# schematic.net
KiCad netlist of a schematic drawn in EAGLE
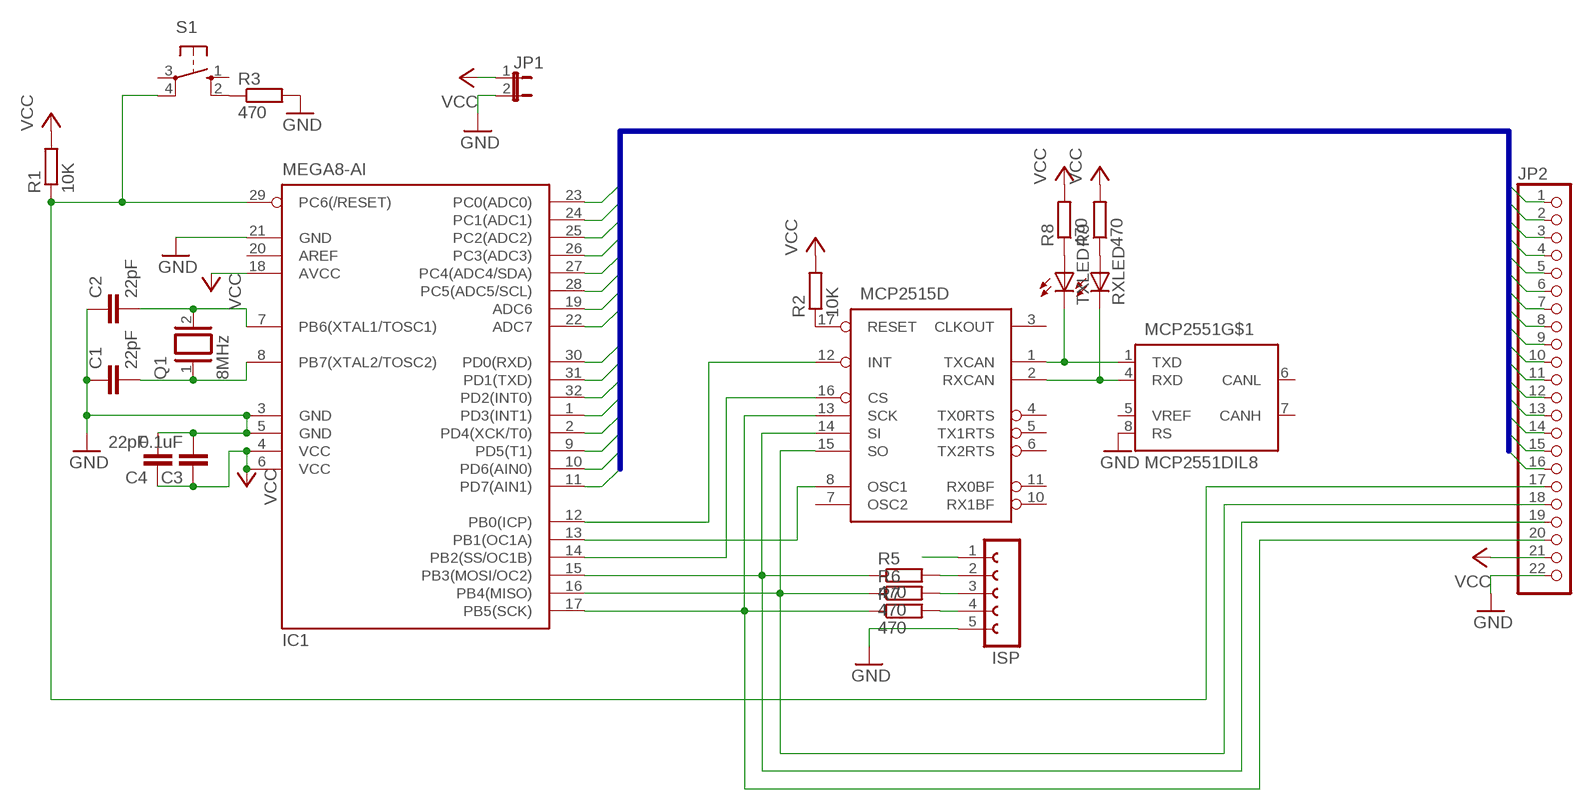
[diagram p0: schematic, sheet 1]

(export (version "E")
  (design (tool "Eeschema 10.0.6"))
  (components
    (comp (ref "C1")
      (value "22pF")
      (footprint "eagle-import:C0603")
      (libsource (lib "eagle-import") (part "C-EUC0603"))
    )
    (comp (ref "C2")
      (value "22pF")
      (footprint "eagle-import:C0603")
      (libsource (lib "eagle-import") (part "C-EUC0603"))
    )
    (comp (ref "C3")
      (value "0.1uF")
      (footprint "eagle-import:C0603")
      (libsource (lib "eagle-import") (part "C-EUC0603"))
    )
    (comp (ref "C4")
      (value "22pF")
      (footprint "eagle-import:C0603")
      (libsource (lib "eagle-import") (part "C-EUC0603"))
    )
    (comp (ref "IC1")
      (value "MEGA8-AI")
      (footprint "eagle-import:TQFP32-08")
      (fields (field (name "MPN") "ATMEGA8-16AU") (field (name "OC_NEWARK") "unknown"))
      (libsource (lib "eagle-import") (part "MEGA8-AI"))
    )
    (comp (ref "ISP")
      (value "FE05-1")
      (footprint "eagle-import:FE05-1")
      (libsource (lib "eagle-import") (part "FE05-1"))
    )
    (comp (ref "JP1")
      (value "JUMPER-2PTH")
      (footprint "eagle-import:1X02")
      (libsource (lib "eagle-import") (part "JUMPER-2PTH"))
    )
    (comp (ref "JP2")
      (value "PINHD-1X22/90")
      (footprint "eagle-import:1X22_90")
      (libsource (lib "eagle-import") (part "PINHD-1X22/90"))
    )
    (comp (ref "MCP2515")
      (value "MCP2515P")
      (footprint "eagle-import:DIL18")
      (libsource (lib "eagle-import") (part "MCP2515P"))
    )
    (comp (ref "MCP2551")
      (value "MCP2551DIL8")
      (footprint "eagle-import:DIL08")
      (libsource (lib "eagle-import") (part "MCP2551DIL8"))
    )
    (comp (ref "Q1")
      (value "8MHz")
      (footprint "eagle-import:QS")
      (libsource (lib "eagle-import") (part "XTAL/S"))
    )
    (comp (ref "R1")
      (value "10K")
      (footprint "eagle-import:R0603")
      (libsource (lib "eagle-import") (part "R-EU_R0603"))
    )
    (comp (ref "R2")
      (value "10K")
      (footprint "eagle-import:R0603")
      (libsource (lib "eagle-import") (part "R-EU_R0603"))
    )
    (comp (ref "R3")
      (value "470")
      (footprint "eagle-import:R0603")
      (libsource (lib "eagle-import") (part "R-EU_R0603"))
    )
    (comp (ref "R5")
      (value "470")
      (footprint "eagle-import:R0603")
      (libsource (lib "eagle-import") (part "R-EU_R0603"))
    )
    (comp (ref "R6")
      (value "470")
      (footprint "eagle-import:R0603")
      (libsource (lib "eagle-import") (part "R-EU_R0603"))
    )
    (comp (ref "R7")
      (value "470")
      (footprint "eagle-import:R0603")
      (libsource (lib "eagle-import") (part "R-EU_R0603"))
    )
    (comp (ref "R8")
      (value "470")
      (footprint "eagle-import:R0603")
      (libsource (lib "eagle-import") (part "R-EU_R0603"))
    )
    (comp (ref "R9")
      (value "470")
      (footprint "eagle-import:R0603")
      (libsource (lib "eagle-import") (part "R-EU_R0603"))
    )
    (comp (ref "RXLED")
      (value "LED")
      (footprint "eagle-import:SMARTLED-TTW")
      (libsource (lib "eagle-import") (part "LED"))
    )
    (comp (ref "S1")
      (value "10-XX")
      (footprint "eagle-import:B3F-10XX")
      (fields (field (name "MPN") "B3F-1000"))
      (libsource (lib "eagle-import") (part "10-XX"))
    )
    (comp (ref "TXLED")
      (value "LED")
      (footprint "eagle-import:SMARTLED-TTW")
      (libsource (lib "eagle-import") (part "LED"))
    )
  )
  (nets
    (net (code "1") (name "/PC0") (class "Default")
      (node (ref "IC1") (pin "23") (pinfunction "PC0(ADC0)_23") (pintype "bidirectional"))
      (node (ref "JP2") (pin "1") (pinfunction "1_1") (pintype "passive"))
    )
    (net (code "2") (name "/PC1") (class "Default")
      (node (ref "IC1") (pin "24") (pinfunction "PC1(ADC1)_24") (pintype "bidirectional"))
      (node (ref "JP2") (pin "2") (pinfunction "2_2") (pintype "passive"))
    )
    (net (code "3") (name "/PC2") (class "Default")
      (node (ref "IC1") (pin "25") (pinfunction "PC2(ADC2)_25") (pintype "bidirectional"))
      (node (ref "JP2") (pin "3") (pinfunction "3_3") (pintype "passive"))
    )
    (net (code "4") (name "/PC3") (class "Default")
      (node (ref "IC1") (pin "26") (pinfunction "PC3(ADC3)_26") (pintype "bidirectional"))
      (node (ref "JP2") (pin "4") (pinfunction "4_4") (pintype "passive"))
    )
    (net (code "5") (name "/PC4") (class "Default")
      (node (ref "IC1") (pin "27") (pinfunction "PC4(ADC4/SDA)_27") (pintype "bidirectional"))
      (node (ref "JP2") (pin "5") (pinfunction "5_5") (pintype "passive"))
    )
    (net (code "6") (name "/PC5") (class "Default")
      (node (ref "IC1") (pin "28") (pinfunction "PC5(ADC5/SCL)_28") (pintype "bidirectional"))
      (node (ref "JP2") (pin "6") (pinfunction "6_6") (pintype "passive"))
    )
    (net (code "7") (name "/PC6") (class "Default")
      (node (ref "IC1") (pin "19") (pinfunction "ADC6_19") (pintype "bidirectional"))
      (node (ref "JP2") (pin "7") (pinfunction "7_7") (pintype "passive"))
    )
    (net (code "8") (name "/PC7") (class "Default")
      (node (ref "IC1") (pin "22") (pinfunction "ADC7_22") (pintype "bidirectional"))
      (node (ref "JP2") (pin "8") (pinfunction "8_8") (pintype "passive"))
    )
    (net (code "9") (name "/PD0") (class "Default")
      (node (ref "IC1") (pin "30") (pinfunction "PD0(RXD)_30") (pintype "bidirectional"))
      (node (ref "JP2") (pin "9") (pinfunction "9_9") (pintype "passive"))
    )
    (net (code "10") (name "/PD1") (class "Default")
      (node (ref "IC1") (pin "31") (pinfunction "PD1(TXD)_31") (pintype "bidirectional"))
      (node (ref "JP2") (pin "10") (pinfunction "10_10") (pintype "passive"))
    )
    (net (code "11") (name "/PD2") (class "Default")
      (node (ref "IC1") (pin "32") (pinfunction "PD2(INT0)_32") (pintype "bidirectional"))
      (node (ref "JP2") (pin "11") (pinfunction "11_11") (pintype "passive"))
    )
    (net (code "12") (name "/PD3") (class "Default")
      (node (ref "IC1") (pin "1") (pinfunction "PD3(INT1)_1") (pintype "bidirectional"))
      (node (ref "JP2") (pin "12") (pinfunction "12_12") (pintype "passive"))
    )
    (net (code "13") (name "/PD4") (class "Default")
      (node (ref "IC1") (pin "2") (pinfunction "PD4(XCK/T0)_2") (pintype "bidirectional"))
      (node (ref "JP2") (pin "13") (pinfunction "13_13") (pintype "passive"))
    )
    (net (code "14") (name "/PD5") (class "Default")
      (node (ref "IC1") (pin "9") (pinfunction "PD5(T1)_9") (pintype "bidirectional"))
      (node (ref "JP2") (pin "14") (pinfunction "14_14") (pintype "passive"))
    )
    (net (code "15") (name "/PD6") (class "Default")
      (node (ref "IC1") (pin "10") (pinfunction "PD6(AIN0)_10") (pintype "bidirectional"))
      (node (ref "JP2") (pin "15") (pinfunction "15_15") (pintype "passive"))
    )
    (net (code "16") (name "/PD7") (class "Default")
      (node (ref "IC1") (pin "11") (pinfunction "PD7(AIN1)_11") (pintype "bidirectional"))
      (node (ref "JP2") (pin "16") (pinfunction "16_16") (pintype "passive"))
    )
    (net (code "17") (name "/RESET") (class "Default")
      (node (ref "IC1") (pin "29") (pinfunction "PC6(/RESET)_29") (pintype "bidirectional"))
      (node (ref "ISP") (pin "1") (pinfunction "1_1") (pintype "passive"))
      (node (ref "JP2") (pin "17") (pinfunction "17_17") (pintype "passive"))
      (node (ref "R1") (pin "1") (pinfunction "1_1") (pintype "passive"))
      (node (ref "S1") (pin "4") (pinfunction "P1_4") (pintype "passive"))
    )
    (net (code "18") (name "GND") (class "Default")
      (node (ref "C1") (pin "1") (pinfunction "1_1") (pintype "passive"))
      (node (ref "C2") (pin "1") (pinfunction "1_1") (pintype "passive"))
      (node (ref "C3") (pin "2") (pinfunction "2_2") (pintype "passive"))
      (node (ref "C4") (pin "2") (pinfunction "2_2") (pintype "passive"))
      (node (ref "IC1") (pin "21") (pinfunction "GND_21") (pintype "power_in"))
      (node (ref "IC1") (pin "3") (pinfunction "GND_3") (pintype "power_in"))
      (node (ref "IC1") (pin "5") (pinfunction "GND_5") (pintype "power_in"))
      (node (ref "ISP") (pin "5") (pinfunction "5_5") (pintype "passive"))
      (node (ref "JP1") (pin "2") (pinfunction "2_2") (pintype "passive"))
      (node (ref "JP2") (pin "22") (pinfunction "22_22") (pintype "passive"))
      (node (ref "MCP2551") (pin "8") (pinfunction "RS_8") (pintype "bidirectional"))
      (node (ref "R3") (pin "2") (pinfunction "2_2") (pintype "passive"))
    )
    (net (code "19") (name "Net-(IC1-PB0(ICP))") (class "Default")
      (node (ref "IC1") (pin "12") (pinfunction "PB0(ICP)_12") (pintype "bidirectional"))
      (node (ref "MCP2515") (pin "12") (pinfunction "INT_12") (pintype "output"))
    )
    (net (code "20") (name "Net-(IC1-PB1(OC1A))") (class "Default")
      (node (ref "IC1") (pin "13") (pinfunction "PB1(OC1A)_13") (pintype "bidirectional"))
      (node (ref "MCP2515") (pin "8") (pinfunction "OSC1_8") (pintype "input"))
    )
    (net (code "21") (name "Net-(IC1-PB2(SS{slash}OC1B))") (class "Default")
      (node (ref "IC1") (pin "14") (pinfunction "PB2(SS/OC1B)_14") (pintype "bidirectional"))
      (node (ref "MCP2515") (pin "16") (pinfunction "CS_16") (pintype "input"))
    )
    (net (code "22") (name "Net-(IC1-PB3(MOSI{slash}OC2))") (class "Default")
      (node (ref "IC1") (pin "15") (pinfunction "PB3(MOSI/OC2)_15") (pintype "bidirectional"))
      (node (ref "JP2") (pin "19") (pinfunction "19_19") (pintype "passive"))
      (node (ref "MCP2515") (pin "14") (pinfunction "SI_14") (pintype "input"))
      (node (ref "R5") (pin "1") (pinfunction "1_1") (pintype "passive"))
    )
    (net (code "23") (name "Net-(IC1-PB4(MISO))") (class "Default")
      (node (ref "IC1") (pin "16") (pinfunction "PB4(MISO)_16") (pintype "bidirectional"))
      (node (ref "JP2") (pin "18") (pinfunction "18_18") (pintype "passive"))
      (node (ref "MCP2515") (pin "15") (pinfunction "SO_15") (pintype "output"))
      (node (ref "R6") (pin "1") (pinfunction "1_1") (pintype "passive"))
    )
    (net (code "24") (name "Net-(IC1-PB5(SCK))") (class "Default")
      (node (ref "IC1") (pin "17") (pinfunction "PB5(SCK)_17") (pintype "bidirectional"))
      (node (ref "JP2") (pin "20") (pinfunction "20_20") (pintype "passive"))
      (node (ref "MCP2515") (pin "13") (pinfunction "SCK_13") (pintype "input"))
      (node (ref "R7") (pin "1") (pinfunction "1_1") (pintype "passive"))
    )
    (net (code "25") (name "Net-(IC1-PB6(XTAL1{slash}TOSC1))") (class "Default")
      (node (ref "C2") (pin "2") (pinfunction "2_2") (pintype "passive"))
      (node (ref "IC1") (pin "7") (pinfunction "PB6(XTAL1/TOSC1)_7") (pintype "bidirectional"))
      (node (ref "Q1") (pin "2") (pinfunction "2_2") (pintype "passive"))
    )
    (net (code "26") (name "Net-(IC1-PB7(XTAL2{slash}TOSC2))") (class "Default")
      (node (ref "C1") (pin "2") (pinfunction "2_2") (pintype "passive"))
      (node (ref "IC1") (pin "8") (pinfunction "PB7(XTAL2/TOSC2)_8") (pintype "bidirectional"))
      (node (ref "Q1") (pin "1") (pinfunction "1_1") (pintype "passive"))
    )
    (net (code "27") (name "Net-(ISP-Pad2)") (class "Default")
      (node (ref "ISP") (pin "2") (pinfunction "2_2") (pintype "passive"))
      (node (ref "R5") (pin "2") (pinfunction "2_2") (pintype "passive"))
    )
    (net (code "28") (name "Net-(ISP-Pad3)") (class "Default")
      (node (ref "ISP") (pin "3") (pinfunction "3_3") (pintype "passive"))
      (node (ref "R6") (pin "2") (pinfunction "2_2") (pintype "passive"))
    )
    (net (code "29") (name "Net-(ISP-Pad4)") (class "Default")
      (node (ref "ISP") (pin "4") (pinfunction "4_4") (pintype "passive"))
      (node (ref "R7") (pin "2") (pinfunction "2_2") (pintype "passive"))
    )
    (net (code "30") (name "Net-(MCP2515A-RESET)") (class "Default")
      (node (ref "MCP2515") (pin "17") (pinfunction "RESET_17") (pintype "input"))
      (node (ref "R2") (pin "1") (pinfunction "1_1") (pintype "passive"))
    )
    (net (code "31") (name "Net-(MCP2515A-RXCAN)") (class "Default")
      (node (ref "MCP2515") (pin "2") (pinfunction "RXCAN_2") (pintype "input"))
      (node (ref "MCP2551") (pin "4") (pinfunction "RXD_4") (pintype "bidirectional"))
      (node (ref "RXLED") (pin "C@1") (pinfunction "C_C@1") (pintype "passive"))
    )
    (net (code "32") (name "Net-(MCP2515A-TXCAN)") (class "Default")
      (node (ref "MCP2515") (pin "1") (pinfunction "TXCAN_1") (pintype "output"))
      (node (ref "MCP2551") (pin "1") (pinfunction "TXD_1") (pintype "bidirectional"))
      (node (ref "TXLED") (pin "C@1") (pinfunction "C_C@1") (pintype "passive"))
    )
    (net (code "33") (name "Net-(RXLED-A)") (class "Default")
      (node (ref "R9") (pin "1") (pinfunction "1_1") (pintype "passive"))
      (node (ref "RXLED") (pin "A@1") (pinfunction "A_A@1") (pintype "passive"))
    )
    (net (code "34") (name "Net-(S1-S1)") (class "Default")
      (node (ref "R3") (pin "1") (pinfunction "1_1") (pintype "passive"))
      (node (ref "S1") (pin "2") (pinfunction "S1_2") (pintype "passive"))
    )
    (net (code "35") (name "Net-(TXLED-A)") (class "Default")
      (node (ref "R8") (pin "1") (pinfunction "1_1") (pintype "passive"))
      (node (ref "TXLED") (pin "A@1") (pinfunction "A_A@1") (pintype "passive"))
    )
    (net (code "36") (name "VCC") (class "Default")
      (node (ref "C3") (pin "1") (pinfunction "1_1") (pintype "passive"))
      (node (ref "C4") (pin "1") (pinfunction "1_1") (pintype "passive"))
      (node (ref "IC1") (pin "18") (pinfunction "AVCC_18") (pintype "power_in"))
      (node (ref "IC1") (pin "4") (pinfunction "VCC_4") (pintype "power_in"))
      (node (ref "IC1") (pin "6") (pinfunction "VCC_6") (pintype "power_in"))
      (node (ref "JP1") (pin "1") (pinfunction "1_1") (pintype "passive"))
      (node (ref "JP2") (pin "21") (pinfunction "21_21") (pintype "passive"))
      (node (ref "R1") (pin "2") (pinfunction "2_2") (pintype "passive"))
      (node (ref "R2") (pin "2") (pinfunction "2_2") (pintype "passive"))
      (node (ref "R8") (pin "2") (pinfunction "2_2") (pintype "passive"))
      (node (ref "R9") (pin "2") (pinfunction "2_2") (pintype "passive"))
    )
    (net (code "37") (name "unconnected-(IC1-AREF-Pad20)") (class "Default")
      (node (ref "IC1") (pin "20") (pinfunction "AREF_20") (pintype "passive"))
    )
    (net (code "38") (name "unconnected-(MCP2515A-CLKOUT-Pad3)") (class "Default")
      (node (ref "MCP2515") (pin "3") (pinfunction "CLKOUT_3") (pintype "output"))
    )
    (net (code "39") (name "unconnected-(MCP2515A-OSC2-Pad7)") (class "Default")
      (node (ref "MCP2515") (pin "7") (pinfunction "OSC2_7") (pintype "input"))
    )
    (net (code "40") (name "unconnected-(MCP2515A-RX0BF-Pad11)") (class "Default")
      (node (ref "MCP2515") (pin "11") (pinfunction "RX0BF_11") (pintype "output"))
    )
    (net (code "41") (name "unconnected-(MCP2515A-RX1BF-Pad10)") (class "Default")
      (node (ref "MCP2515") (pin "10") (pinfunction "RX1BF_10") (pintype "output"))
    )
    (net (code "42") (name "unconnected-(MCP2515A-TX0RTS-Pad4)") (class "Default")
      (node (ref "MCP2515") (pin "4") (pinfunction "TX0RTS_4") (pintype "input"))
    )
    (net (code "43") (name "unconnected-(MCP2515A-TX1RTS-Pad5)") (class "Default")
      (node (ref "MCP2515") (pin "5") (pinfunction "TX1RTS_5") (pintype "input"))
    )
    (net (code "44") (name "unconnected-(MCP2515A-TX2RTS-Pad6)") (class "Default")
      (node (ref "MCP2515") (pin "6") (pinfunction "TX2RTS_6") (pintype "input"))
    )
    (net (code "45") (name "unconnected-(MCP2551A-CANH-Pad7)") (class "Default")
      (node (ref "MCP2551") (pin "7") (pinfunction "CANH_7") (pintype "bidirectional"))
    )
    (net (code "46") (name "unconnected-(MCP2551A-CANL-Pad6)") (class "Default")
      (node (ref "MCP2551") (pin "6") (pinfunction "CANL_6") (pintype "bidirectional"))
    )
    (net (code "47") (name "unconnected-(MCP2551A-VREF-Pad5)") (class "Default")
      (node (ref "MCP2551") (pin "5") (pinfunction "VREF_5") (pintype "bidirectional"))
    )
    (net (code "48") (name "unconnected-(S1-P-Pad3)") (class "Default")
      (node (ref "S1") (pin "3") (pinfunction "P_3") (pintype "passive"))
    )
    (net (code "49") (name "unconnected-(S1-S-Pad1)") (class "Default")
      (node (ref "S1") (pin "1") (pinfunction "S_1") (pintype "passive"))
    )
  )
)
